# processor_toycathon_v5.net
KiCad netlist of a schematic drawn in EAGLE
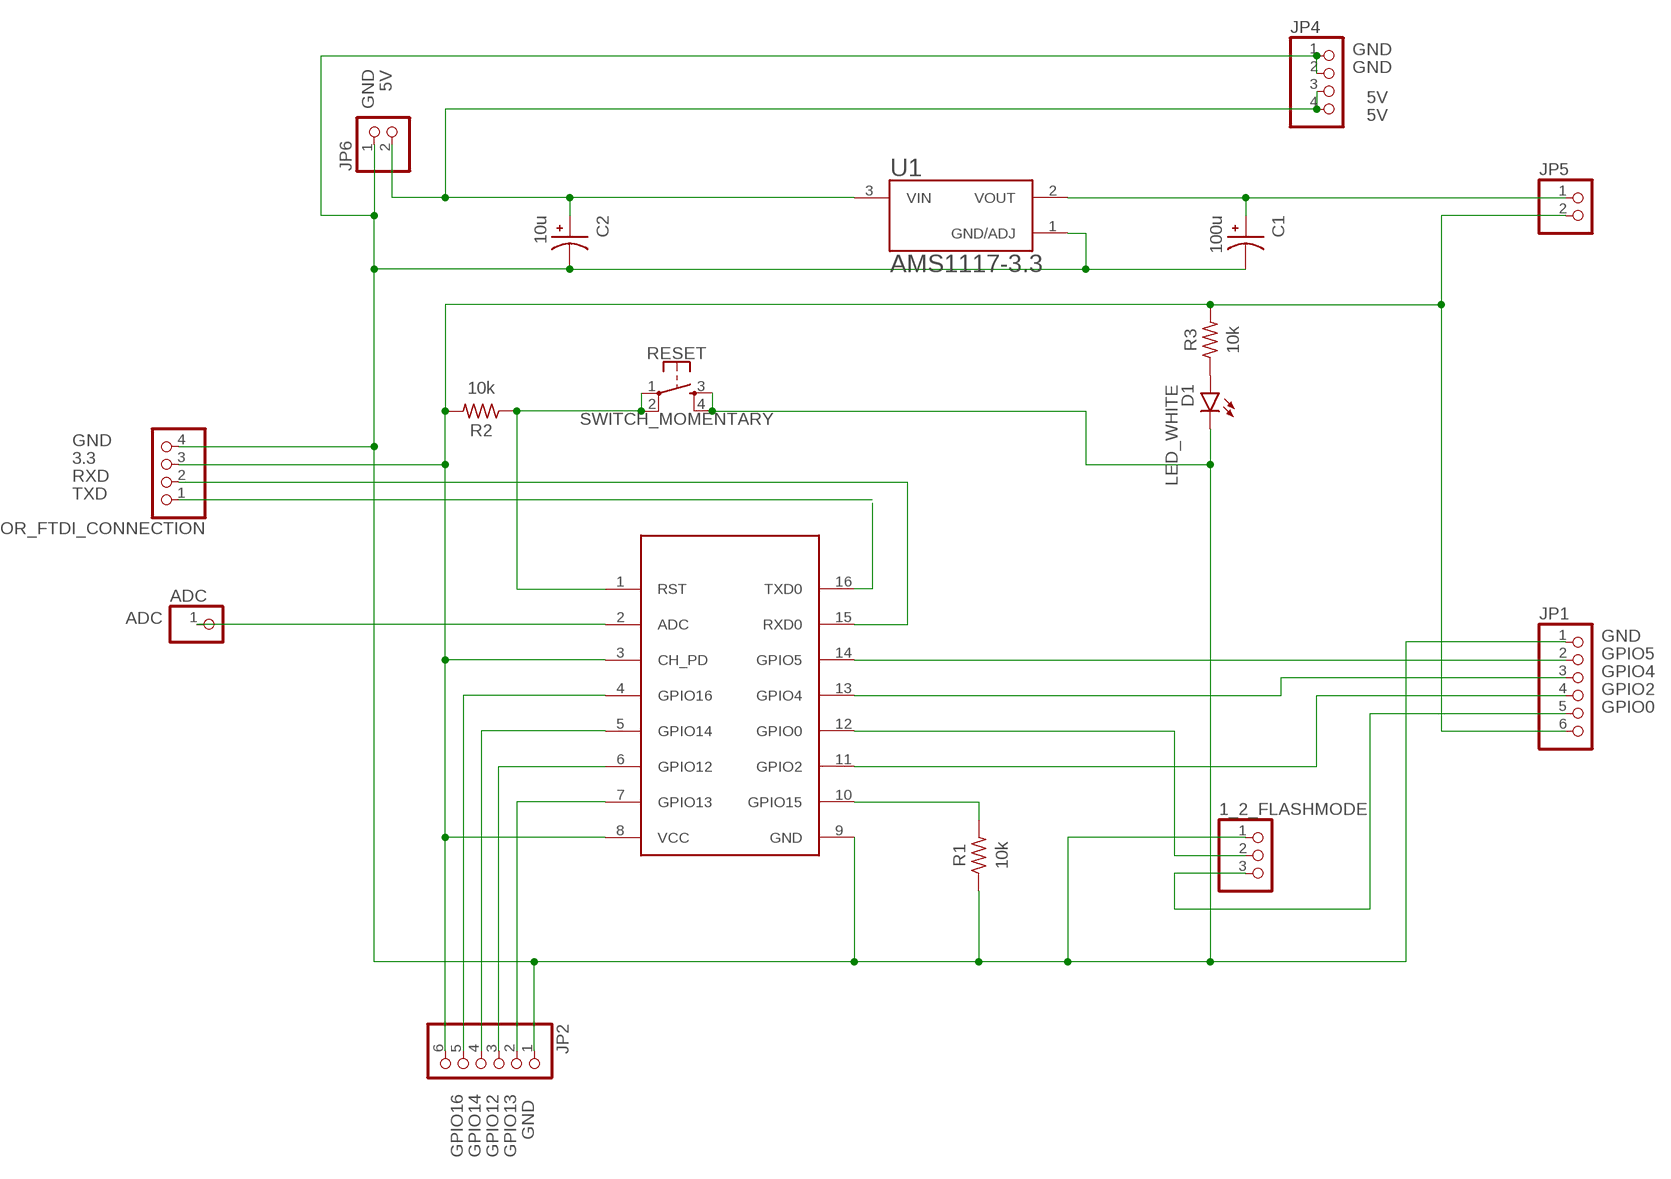
[diagram p0: schematic, sheet 1]

(export (version "E")
  (design (tool "Eeschema 10.0.6"))
  (components
    (comp (ref "1_2_FLASHMODE")
      (value "PINHD-1X3")
      (footprint "eagle-import:1X03")
      (libsource (lib "eagle-import") (part "PINHD-1X3"))
    )
    (comp (ref "ADC")
      (value "PINHD-1X1")
      (footprint "eagle-import:1X01")
      (libsource (lib "eagle-import") (part "PINHD-1X1"))
    )
    (comp (ref "C1")
      (value "100u")
      (footprint "eagle-import:CAPPRD250W50D500H1100")
      (fields (field (name "MF") "Panasonic") (field (name "MP") "ECE-A1EN220XI"))
      (libsource (lib "eagle-import") (part "ECEA1EN220XI"))
    )
    (comp (ref "C2")
      (value "10u")
      (footprint "eagle-import:CAPPRD250W50D500H1100")
      (fields (field (name "MF") "Panasonic") (field (name "MP") "ECE-A1EN220XI"))
      (libsource (lib "eagle-import") (part "ECEA1EN220XI"))
    )
    (comp (ref "D1")
      (value "LED_WHITE")
      (footprint "eagle-import:LEDRD254W60D565H860B_W")
      (libsource (lib "eagle-import") (part "LED_RADIALWHITE_"))
    )
    (comp (ref "FOR_FTDI_CONNECTION")
      (value "PINHD-1X4")
      (footprint "eagle-import:1X04")
      (libsource (lib "eagle-import") (part "PINHD-1X4"))
    )
    (comp (ref "JP1")
      (value "PINHD-1X6")
      (footprint "eagle-import:1X06")
      (libsource (lib "eagle-import") (part "PINHD-1X6"))
    )
    (comp (ref "JP2")
      (value "PINHD-1X6")
      (footprint "eagle-import:1X06")
      (libsource (lib "eagle-import") (part "PINHD-1X6"))
    )
    (comp (ref "JP4")
      (value "PINHD-1X4")
      (footprint "eagle-import:1X04")
      (libsource (lib "eagle-import") (part "PINHD-1X4"))
    )
    (comp (ref "JP5")
      (value "PINHD-1X2")
      (footprint "eagle-import:1X02")
      (libsource (lib "eagle-import") (part "PINHD-1X2"))
    )
    (comp (ref "JP6")
      (value "PINHD-1X2")
      (footprint "eagle-import:1X02")
      (libsource (lib "eagle-import") (part "PINHD-1X2"))
    )
    (comp (ref "R1")
      (value "10k")
      (footprint "eagle-import:RESAD724W46L381D178B")
      (libsource (lib "eagle-import") (part "R-USAXIAL-7.2MM-PITCH_"))
    )
    (comp (ref "R2")
      (value "10k")
      (footprint "eagle-import:RESAD724W46L381D178B")
      (libsource (lib "eagle-import") (part "R-USAXIAL-7.2MM-PITCH_"))
    )
    (comp (ref "R3")
      (value "10k")
      (footprint "eagle-import:RESAD724W46L381D178B")
      (libsource (lib "eagle-import") (part "R-USAXIAL-7.2MM-PITCH_"))
    )
    (comp (ref "RESET")
      (value "SWITCH_MOMENTARY")
      (footprint "eagle-import:SWITCH-MOMENTARY-PTH-6.5MM")
      (libsource (lib "eagle-import") (part "SWITCH_MOMENTARY"))
    )
    (comp (ref "U$1")
      (value "ESP-07")
      (footprint "eagle-import:ESP-07")
      (fields (field (name "MF") "RF Solutions Ltd"))
      (libsource (lib "eagle-import") (part "ESP-07"))
    )
    (comp (ref "U1")
      (value "AMS1117-3.3")
      (footprint "eagle-import:SOT229P700X180-4N")
      (fields (field (name "MF") "Advanced Monolithic Systems"))
      (libsource (lib "eagle-import") (part "AMS1117-3.3"))
    )
  )
  (nets
    (net (code "1") (name "/3.3") (class "Default")
      (node (ref "FOR_FTDI_CONNECTION") (pin "3") (pinfunction "3_3") (pintype "passive"))
      (node (ref "JP1") (pin "6") (pinfunction "6_6") (pintype "passive"))
      (node (ref "JP2") (pin "6") (pinfunction "6_6") (pintype "passive"))
      (node (ref "JP5") (pin "2") (pinfunction "2_2") (pintype "passive"))
      (node (ref "R2") (pin "2") (pinfunction "2_2") (pintype "passive"))
      (node (ref "R3") (pin "2") (pinfunction "2_2") (pintype "passive"))
      (node (ref "U$1") (pin "3") (pinfunction "CH_PD_3") (pintype "bidirectional"))
      (node (ref "U$1") (pin "8") (pinfunction "VCC_8") (pintype "bidirectional"))
    )
    (net (code "2") (name "/5V") (class "Default")
      (node (ref "C2") (pin "P") (pinfunction "P_P") (pintype "passive"))
      (node (ref "JP4") (pin "3") (pinfunction "3_3") (pintype "passive"))
      (node (ref "JP4") (pin "4") (pinfunction "4_4") (pintype "passive"))
      (node (ref "JP6") (pin "2") (pinfunction "2_2") (pintype "passive"))
      (node (ref "U1") (pin "3") (pinfunction "VIN_3") (pintype "input"))
    )
    (net (code "3") (name "/ADC") (class "Default")
      (node (ref "ADC") (pin "1") (pinfunction "1_1") (pintype "passive"))
      (node (ref "U$1") (pin "2") (pinfunction "ADC_2") (pintype "bidirectional"))
    )
    (net (code "4") (name "/GND") (class "Default")
      (node (ref "1_2_FLASHMODE") (pin "1") (pinfunction "1_1") (pintype "passive"))
      (node (ref "C1") (pin "N") (pinfunction "N_N") (pintype "passive"))
      (node (ref "C2") (pin "N") (pinfunction "N_N") (pintype "passive"))
      (node (ref "D1") (pin "2") (pinfunction "C_2") (pintype "passive"))
      (node (ref "FOR_FTDI_CONNECTION") (pin "4") (pinfunction "4_4") (pintype "passive"))
      (node (ref "JP1") (pin "1") (pinfunction "1_1") (pintype "passive"))
      (node (ref "JP2") (pin "1") (pinfunction "1_1") (pintype "passive"))
      (node (ref "JP4") (pin "1") (pinfunction "1_1") (pintype "passive"))
      (node (ref "JP4") (pin "2") (pinfunction "2_2") (pintype "passive"))
      (node (ref "JP6") (pin "1") (pinfunction "1_1") (pintype "passive"))
      (node (ref "R1") (pin "1") (pinfunction "1_1") (pintype "passive"))
      (node (ref "RESET") (pin "3") (pinfunction "3_3") (pintype "passive"))
      (node (ref "RESET") (pin "4") (pinfunction "4_4") (pintype "passive"))
      (node (ref "U$1") (pin "9") (pinfunction "GND_9") (pintype "bidirectional"))
      (node (ref "U1") (pin "1") (pinfunction "GND/ADJ_1") (pintype "power_in"))
    )
    (net (code "5") (name "/GPIO0") (class "Default")
      (node (ref "1_2_FLASHMODE") (pin "3") (pinfunction "3_3") (pintype "passive"))
      (node (ref "JP1") (pin "5") (pinfunction "5_5") (pintype "passive"))
    )
    (net (code "6") (name "/GPIO2") (class "Default")
      (node (ref "JP1") (pin "4") (pinfunction "4_4") (pintype "passive"))
      (node (ref "U$1") (pin "11") (pinfunction "GPIO2_11") (pintype "bidirectional"))
    )
    (net (code "7") (name "/GPIO4") (class "Default")
      (node (ref "JP1") (pin "3") (pinfunction "3_3") (pintype "passive"))
      (node (ref "U$1") (pin "13") (pinfunction "GPIO4_13") (pintype "bidirectional"))
    )
    (net (code "8") (name "/GPIO5") (class "Default")
      (node (ref "JP1") (pin "2") (pinfunction "2_2") (pintype "passive"))
      (node (ref "U$1") (pin "14") (pinfunction "GPIO5_14") (pintype "bidirectional"))
    )
    (net (code "9") (name "/GPIO12") (class "Default")
      (node (ref "JP2") (pin "3") (pinfunction "3_3") (pintype "passive"))
      (node (ref "U$1") (pin "6") (pinfunction "GPIO12_6") (pintype "bidirectional"))
    )
    (net (code "10") (name "/GPIO13") (class "Default")
      (node (ref "JP2") (pin "2") (pinfunction "2_2") (pintype "passive"))
      (node (ref "U$1") (pin "7") (pinfunction "GPIO13_7") (pintype "bidirectional"))
    )
    (net (code "11") (name "/GPIO14") (class "Default")
      (node (ref "JP2") (pin "4") (pinfunction "4_4") (pintype "passive"))
      (node (ref "U$1") (pin "5") (pinfunction "GPIO14_5") (pintype "bidirectional"))
    )
    (net (code "12") (name "/GPIO16") (class "Default")
      (node (ref "JP2") (pin "5") (pinfunction "5_5") (pintype "passive"))
      (node (ref "U$1") (pin "4") (pinfunction "GPIO16_4") (pintype "bidirectional"))
    )
    (net (code "13") (name "/RXD") (class "Default")
      (node (ref "FOR_FTDI_CONNECTION") (pin "2") (pinfunction "2_2") (pintype "passive"))
      (node (ref "U$1") (pin "15") (pinfunction "RXD0_15") (pintype "bidirectional"))
    )
    (net (code "14") (name "/TXD") (class "Default")
      (node (ref "FOR_FTDI_CONNECTION") (pin "1") (pinfunction "1_1") (pintype "passive"))
    )
    (net (code "15") (name "Net-(D1-A)") (class "Default")
      (node (ref "D1") (pin "1") (pinfunction "A_1") (pintype "passive"))
      (node (ref "R3") (pin "1") (pinfunction "1_1") (pintype "passive"))
    )
    (net (code "16") (name "Net-(U$1-GPIO0)") (class "Default")
      (node (ref "1_2_FLASHMODE") (pin "2") (pinfunction "2_2") (pintype "passive"))
      (node (ref "U$1") (pin "12") (pinfunction "GPIO0_12") (pintype "bidirectional"))
    )
    (net (code "17") (name "Net-(U$1-GPIO15)") (class "Default")
      (node (ref "R1") (pin "2") (pinfunction "2_2") (pintype "passive"))
      (node (ref "U$1") (pin "10") (pinfunction "GPIO15_10") (pintype "bidirectional"))
    )
    (net (code "18") (name "Net-(U$1-RST)") (class "Default")
      (node (ref "R2") (pin "1") (pinfunction "1_1") (pintype "passive"))
      (node (ref "RESET") (pin "1") (pinfunction "1_1") (pintype "passive"))
      (node (ref "RESET") (pin "2") (pinfunction "2_2") (pintype "passive"))
      (node (ref "U$1") (pin "1") (pinfunction "RST_1") (pintype "bidirectional"))
    )
    (net (code "19") (name "Net-(U1-VOUT)") (class "Default")
      (node (ref "C1") (pin "P") (pinfunction "P_P") (pintype "passive"))
      (node (ref "JP5") (pin "1") (pinfunction "1_1") (pintype "passive"))
      (node (ref "U1") (pin "2") (pinfunction "VOUT_2") (pintype "output"))
    )
    (net (code "20") (name "unconnected-(U$1-TXD0-Pad16)") (class "Default")
      (node (ref "U$1") (pin "16") (pinfunction "TXD0_16") (pintype "bidirectional"))
    )
  )
)
